# ATRACK_HOST_V1.net
KiCad netlist of a schematic drawn in Altium Designer
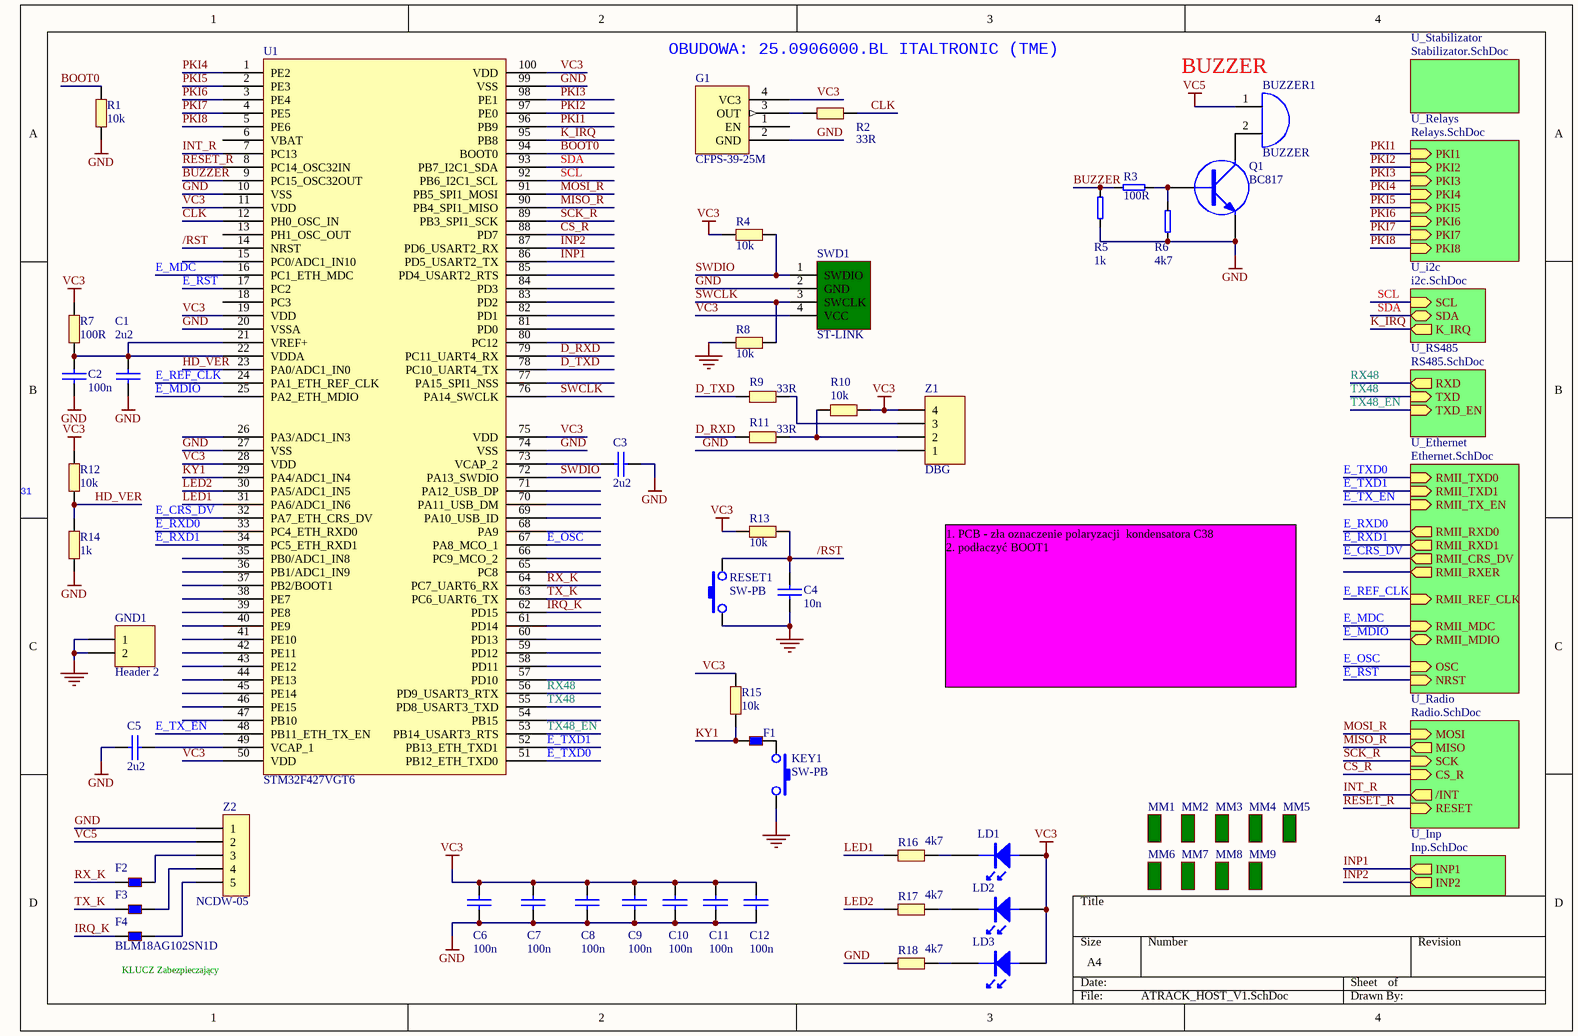
[diagram p0: ATRACK_HOST_V1.SchDoc]

(export (version "E")
  (design (tool "Eeschema 10.0.6"))
  (components
    (comp (ref "BUZZER1") (value "BUZZER") (footprint "BMT-1205H09B") (libsource (lib "*") (part "BUZZER")))
    (comp (ref "C1")
      (value "2u2")
      (footprint "0603C")
      (description "Capacitor")
      (libsource (lib "*") (part "CAP"))
    )
    (comp (ref "C2")
      (value "100n")
      (footprint "0603C")
      (description "Capacitor")
      (libsource (lib "*") (part "CAP"))
    )
    (comp (ref "C3")
      (value "2u2")
      (footprint "0603C")
      (description "Capacitor")
      (libsource (lib "*") (part "CAP"))
    )
    (comp (ref "C4")
      (value "10n")
      (footprint "0603C")
      (description "Capacitor")
      (libsource (lib "*") (part "CAP"))
    )
    (comp (ref "C5")
      (value "2u2")
      (footprint "0603C")
      (description "Capacitor")
      (libsource (lib "*") (part "CAP"))
    )
    (comp (ref "C6")
      (value "100n")
      (footprint "0603C")
      (description "Capacitor")
      (libsource (lib "*") (part "CAP"))
    )
    (comp (ref "C7")
      (value "100n")
      (footprint "0603C")
      (description "Capacitor")
      (libsource (lib "*") (part "CAP"))
    )
    (comp (ref "C8")
      (value "100n")
      (footprint "0603C")
      (description "Capacitor")
      (libsource (lib "*") (part "CAP"))
    )
    (comp (ref "C9")
      (value "100n")
      (footprint "0603C")
      (description "Capacitor")
      (libsource (lib "*") (part "CAP"))
    )
    (comp (ref "C10")
      (value "100n")
      (footprint "0603C")
      (description "Capacitor")
      (libsource (lib "*") (part "CAP"))
    )
    (comp (ref "C11")
      (value "100n")
      (footprint "0603C")
      (description "Capacitor")
      (libsource (lib "*") (part "CAP"))
    )
    (comp (ref "C12")
      (value "100n")
      (footprint "0603C")
      (description "Capacitor")
      (libsource (lib "*") (part "CAP"))
    )
    (comp (ref "F1")
      (value "BLM18BB141SN1D")
      (footprint "0603L")
      (description "Koralik ferrytowy")
      (libsource (lib "*") (part "1812"))
    )
    (comp (ref "F2")
      (value "BLM18AG102SN1D")
      (footprint "0603L")
      (description "Koralik ferrytowy")
      (libsource (lib "*") (part "KORALIK"))
    )
    (comp (ref "F3")
      (value "BLM18AG102SN1D")
      (footprint "0603L")
      (description "Koralik ferrytowy")
      (libsource (lib "*") (part "KORALIK"))
    )
    (comp (ref "F4")
      (value "BLM18AG102SN1D")
      (footprint "0603L")
      (description "Koralik ferrytowy")
      (libsource (lib "*") (part "KORALIK"))
    )
    (comp (ref "G1") (value "CFPS-39-25M") (footprint "GEN_SMD1_1") (libsource (lib "*") (part "GENER_SMD")))
    (comp (ref "GND1")
      (value "Header 2")
      (footprint "HDR1X2")
      (description "Header, 2-Pin")
      (fields (field (name "PUBLISHER") "Altium Limited"))
      (libsource (lib "Miscellaneous Connectors") (part "Header 2"))
    )
    (comp (ref "KEY1") (value "SW-PB") (footprint "DTSM31N_2") (libsource (lib "*") (part "SW-PB")))
    (comp (ref "LD1") (value "~") (footprint "0805LG") (libsource (lib "*") (part "LED")))
    (comp (ref "LD2") (value "~") (footprint "0805LR") (libsource (lib "*") (part "LED")))
    (comp (ref "LD3") (value "~") (footprint "0805LG") (libsource (lib "*") (part "LED")))
    (comp (ref "MM1") (value "~") (footprint "REF_CIR") (libsource (lib "*") (part "MECH")))
    (comp (ref "MM2") (value "~") (footprint "REF_CIR") (libsource (lib "*") (part "MECH")))
    (comp (ref "MM3") (value "~") (footprint "REF_SQR") (libsource (lib "*") (part "MECH")))
    (comp (ref "MM4") (value "~") (footprint "REF_SQR") (libsource (lib "*") (part "MECH")))
    (comp (ref "MM5") (value "~") (footprint "PB_FREE_GRAF") (libsource (lib "*") (part "MECH")))
    (comp (ref "MM6") (value "~") (footprint "REF_CIR") (libsource (lib "*") (part "MECH")))
    (comp (ref "MM7") (value "~") (footprint "REF_CIR") (libsource (lib "*") (part "MECH")))
    (comp (ref "MM8") (value "~") (footprint "REF_SQR") (libsource (lib "*") (part "MECH")))
    (comp (ref "MM9") (value "~") (footprint "REF_SQR") (libsource (lib "*") (part "MECH")))
    (comp (ref "Q1")
      (value "BC817")
      (footprint "SOT23-3Q")
      (description "NPN Transistor")
      (libsource (lib "*") (part "NPN-SOT23"))
    )
    (comp (ref "R1") (value "10k") (footprint "0603R") (libsource (lib "") (part "RES3_3")))
    (comp (ref "R2") (value "33R") (footprint "0603R") (libsource (lib "") (part "RES3_1")))
    (comp (ref "R3") (value "100R") (footprint "0603R") (libsource (lib "*") (part "R")))
    (comp (ref "R4") (value "10k") (footprint "0603R") (libsource (lib "") (part "RES3_2")))
    (comp (ref "R5") (value "1k") (footprint "0603R") (libsource (lib "*") (part "R")))
    (comp (ref "R6") (value "4k7") (footprint "0603R") (libsource (lib "*") (part "R")))
    (comp (ref "R7") (value "100R") (footprint "0603R") (libsource (lib "") (part "RES3_1")))
    (comp (ref "R8") (value "10k") (footprint "0603R") (libsource (lib "") (part "RES3_2")))
    (comp (ref "R9") (value "33R") (footprint "0603R") (libsource (lib "*") (part "RES3")))
    (comp (ref "R10") (value "10k") (footprint "0603R") (libsource (lib "") (part "RES3_2")))
    (comp (ref "R11") (value "33R") (footprint "0603R") (libsource (lib "*") (part "RES3")))
    (comp (ref "R12") (value "10k") (footprint "0603R") (libsource (lib "") (part "RES3_1")))
    (comp (ref "R13") (value "10k") (footprint "0603R") (libsource (lib "") (part "RES3_2")))
    (comp (ref "R14") (value "1k") (footprint "0603R") (libsource (lib "") (part "RES3_1")))
    (comp (ref "R15") (value "10k") (footprint "0603R") (libsource (lib "") (part "RES3_1")))
    (comp (ref "R16") (value "4k7") (footprint "0603R") (libsource (lib "*") (part "RES3")))
    (comp (ref "R17") (value "4k7") (footprint "0603R") (libsource (lib "*") (part "RES3")))
    (comp (ref "R18") (value "4k7") (footprint "0603R") (libsource (lib "*") (part "RES3")))
    (comp (ref "RESET1") (value "SW-PB") (footprint "DTSM31N_2") (libsource (lib "*") (part "SW-PB")))
    (comp (ref "SWD1")
      (value "ST-LINK")
      (footprint "PIN4")
      (description "Header, 4-Pin")
      (fields (field (name "PUBLISHER") "Altium Limited"))
      (libsource (lib "GkSchlib") (part "SW_CON"))
    )
    (comp (ref "U1")
      (value "STM32F427VGT6")
      (footprint "VQ100_2")
      (libsource (lib "GkSchlib") (part "STM32F427_LQFP100"))
    )
    (comp (ref "Z1")
      (value "DBG")
      (footprint "PIN4")
      (description "Header, 4-Pin")
      (fields (field (name "PUBLISHER") "Altium Limited"))
      (libsource (lib "Miscellaneous Connectors") (part "Header 4"))
    )
    (comp (ref "Z2")
      (value "NCDW-05")
      (footprint "KEY_LOG")
      (description "Connector")
      (libsource (lib "*") (part "CON5"))
    )
  )
  (nets
    (net (code "1") (name "/BOOT0") (class "Default")
      (node (ref "R1") (pin "1") (pintype "passive"))
      (node (ref "U1") (pin "94") (pinfunction "BOOT0_94") (pintype "passive"))
    )
    (net (code "2") (name "/BUZZER") (class "Default")
      (node (ref "R3") (pin "2") (pinfunction "2_2") (pintype "passive"))
      (node (ref "R5") (pin "1") (pinfunction "1_1") (pintype "passive"))
      (node (ref "U1") (pin "9") (pinfunction "PC15_OSC32OUT_9") (pintype "passive"))
    )
    (net (code "3") (name "/CLK") (class "Default")
      (node (ref "R2") (pin "2") (pintype "passive"))
      (node (ref "U1") (pin "12") (pinfunction "PH0_OSC_IN_12") (pintype "passive"))
    )
    (net (code "4") (name "/CS_R") (class "Default")
      (node (ref "U1") (pin "88") (pinfunction "PD7_88") (pintype "passive"))
    )
    (net (code "5") (name "/D_RXD") (class "Default")
      (node (ref "R11") (pin "2") (pintype "passive"))
      (node (ref "U1") (pin "79") (pinfunction "PC11_UART4_RX_79") (pintype "passive"))
    )
    (net (code "6") (name "/D_TXD") (class "Default")
      (node (ref "R9") (pin "2") (pintype "passive"))
      (node (ref "U1") (pin "78") (pinfunction "PC10_UART4_TX_78") (pintype "passive"))
    )
    (net (code "7") (name "/E_CRS_DV") (class "Default")
      (node (ref "U1") (pin "32") (pinfunction "PA7_ETH_CRS_DV_32") (pintype "passive"))
    )
    (net (code "8") (name "/E_MDC") (class "Default")
      (node (ref "U1") (pin "16") (pinfunction "PC1_ETH_MDC_16") (pintype "passive"))
    )
    (net (code "9") (name "/E_MDIO") (class "Default")
      (node (ref "U1") (pin "25") (pinfunction "PA2_ETH_MDIO_25") (pintype "passive"))
    )
    (net (code "10") (name "/E_OSC") (class "Default")
      (node (ref "U1") (pin "67") (pinfunction "PA8_MCO_1_67") (pintype "passive"))
    )
    (net (code "11") (name "/E_REF_CLK") (class "Default")
      (node (ref "U1") (pin "24") (pinfunction "PA1_ETH_REF_CLK_24") (pintype "passive"))
    )
    (net (code "12") (name "/E_RST") (class "Default")
      (node (ref "U1") (pin "17") (pinfunction "PC2_17") (pintype "passive"))
    )
    (net (code "13") (name "/E_RXD0") (class "Default")
      (node (ref "U1") (pin "33") (pinfunction "PC4_ETH_RXD0_33") (pintype "passive"))
    )
    (net (code "14") (name "/E_RXD1") (class "Default")
      (node (ref "U1") (pin "34") (pinfunction "PC5_ETH_RXD1_34") (pintype "passive"))
    )
    (net (code "15") (name "/E_TXD0") (class "Default")
      (node (ref "U1") (pin "51") (pinfunction "PB12_ETH_TXD0_51") (pintype "passive"))
    )
    (net (code "16") (name "/E_TXD1") (class "Default")
      (node (ref "U1") (pin "52") (pinfunction "PB13_ETH_TXD1_52") (pintype "passive"))
    )
    (net (code "17") (name "/E_TX_EN") (class "Default")
      (node (ref "U1") (pin "48") (pinfunction "PB11_ETH_TX_EN_48") (pintype "passive"))
    )
    (net (code "18") (name "/HD_VER") (class "Default")
      (node (ref "R12") (pin "1") (pintype "passive"))
      (node (ref "R14") (pin "2") (pintype "passive"))
      (node (ref "U1") (pin "23") (pinfunction "PA0/ADC1_IN0_23") (pintype "passive"))
    )
    (net (code "19") (name "/INP1") (class "Default")
      (node (ref "U1") (pin "86") (pinfunction "PD5_USART2_TX_86") (pintype "passive"))
    )
    (net (code "20") (name "/INP2") (class "Default")
      (node (ref "U1") (pin "87") (pinfunction "PD6_USART2_RX_87") (pintype "passive"))
    )
    (net (code "21") (name "/INT_R") (class "Default")
      (node (ref "U1") (pin "7") (pinfunction "PC13_7") (pintype "passive"))
    )
    (net (code "22") (name "/IRQ_K") (class "Default")
      (node (ref "F4") (pin "1") (pintype "passive"))
      (node (ref "U1") (pin "62") (pinfunction "PD15_62") (pintype "passive"))
    )
    (net (code "23") (name "/KY1") (class "Default")
      (node (ref "F1") (pin "2") (pintype "passive"))
      (node (ref "R15") (pin "1") (pintype "passive"))
      (node (ref "U1") (pin "29") (pinfunction "PA4/ADC1_IN4_29") (pintype "passive"))
    )
    (net (code "24") (name "/K_IRQ") (class "Default")
      (node (ref "U1") (pin "95") (pinfunction "PB8_95") (pintype "passive"))
    )
    (net (code "25") (name "/LED1") (class "Default")
      (node (ref "R16") (pin "2") (pintype "passive"))
      (node (ref "U1") (pin "31") (pinfunction "PA6/ADC1_IN6_31") (pintype "passive"))
    )
    (net (code "26") (name "/LED2") (class "Default")
      (node (ref "R17") (pin "2") (pintype "passive"))
      (node (ref "U1") (pin "30") (pinfunction "PA5/ADC1_IN5_30") (pintype "passive"))
    )
    (net (code "27") (name "/MISO_R") (class "Default")
      (node (ref "U1") (pin "90") (pinfunction "PB4_SPI1_MISO_90") (pintype "passive"))
    )
    (net (code "28") (name "/MOSI_R") (class "Default")
      (node (ref "U1") (pin "91") (pinfunction "PB5_SPI1_MOSI_91") (pintype "passive"))
    )
    (net (code "29") (name "/PKI1") (class "Default")
      (node (ref "U1") (pin "96") (pinfunction "PB9_96") (pintype "passive"))
    )
    (net (code "30") (name "/PKI2") (class "Default")
      (node (ref "U1") (pin "97") (pinfunction "PE0_97") (pintype "passive"))
    )
    (net (code "31") (name "/PKI3") (class "Default")
      (node (ref "U1") (pin "98") (pinfunction "PE1_98") (pintype "passive"))
    )
    (net (code "32") (name "/PKI4") (class "Default")
      (node (ref "U1") (pin "1") (pinfunction "PE2_1") (pintype "passive"))
    )
    (net (code "33") (name "/PKI5") (class "Default")
      (node (ref "U1") (pin "2") (pinfunction "PE3_2") (pintype "passive"))
    )
    (net (code "34") (name "/PKI6") (class "Default")
      (node (ref "U1") (pin "3") (pinfunction "PE4_3") (pintype "passive"))
    )
    (net (code "35") (name "/PKI7") (class "Default")
      (node (ref "U1") (pin "4") (pinfunction "PE5_4") (pintype "passive"))
    )
    (net (code "36") (name "/PKI8") (class "Default")
      (node (ref "U1") (pin "5") (pinfunction "PE6_5") (pintype "passive"))
    )
    (net (code "37") (name "/RESET_R") (class "Default")
      (node (ref "U1") (pin "8") (pinfunction "PC14_OSC32IN_8") (pintype "passive"))
    )
    (net (code "39") (name "/RX48") (class "Default")
      (node (ref "U1") (pin "56") (pinfunction "PD9_USART3_RTX_56") (pintype "passive"))
    )
    (net (code "40") (name "/RX_K") (class "Default")
      (node (ref "F2") (pin "1") (pintype "passive"))
      (node (ref "U1") (pin "64") (pinfunction "PC7_UART6_RX_64") (pintype "passive"))
    )
    (net (code "41") (name "/SCK_R") (class "Default")
      (node (ref "U1") (pin "89") (pinfunction "PB3_SPI1_SCK_89") (pintype "passive"))
    )
    (net (code "42") (name "/SCL") (class "Default")
      (node (ref "U1") (pin "92") (pinfunction "PB6_I2C1_SCL_92") (pintype "passive"))
    )
    (net (code "43") (name "/SDA") (class "Default")
      (node (ref "U1") (pin "93") (pinfunction "PB7_I2C1_SDA_93") (pintype "passive"))
    )
    (net (code "44") (name "/SWCLK") (class "Default")
      (node (ref "R8") (pin "2") (pintype "passive"))
      (node (ref "SWD1") (pin "3") (pinfunction "SWCLK_3") (pintype "passive"))
      (node (ref "U1") (pin "76") (pinfunction "PA14_SWCLK_76") (pintype "passive"))
    )
    (net (code "45") (name "/SWDIO") (class "Default")
      (node (ref "R4") (pin "2") (pintype "passive"))
      (node (ref "SWD1") (pin "1") (pinfunction "SWDIO_1") (pintype "passive"))
      (node (ref "U1") (pin "72") (pinfunction "PA13_SWDIO_72") (pintype "passive"))
    )
    (net (code "46") (name "/TX48") (class "Default")
      (node (ref "U1") (pin "55") (pinfunction "PD8_USART3_TXD_55") (pintype "passive"))
    )
    (net (code "47") (name "/TX48_EN") (class "Default")
      (node (ref "U1") (pin "53") (pinfunction "PB14_USART3_RTS_53") (pintype "passive"))
    )
    (net (code "48") (name "/TX_K") (class "Default")
      (node (ref "F3") (pin "1") (pintype "passive"))
      (node (ref "U1") (pin "63") (pinfunction "PC6_UART6_TX_63") (pintype "passive"))
    )
    (net (code "49") (name "/{slash}RST") (class "Default")
      (node (ref "C4") (pin "1") (pinfunction "1_1") (pintype "passive"))
      (node (ref "R13") (pin "2") (pintype "passive"))
      (node (ref "RESET1") (pin "2") (pinfunction "2_2") (pintype "passive"))
      (node (ref "U1") (pin "14") (pinfunction "NRST_14") (pintype "passive"))
    )
    (net (code "50") (name "GND") (class "Default")
      (node (ref "C1") (pin "2") (pinfunction "2_2") (pintype "passive"))
      (node (ref "C10") (pin "2") (pinfunction "2_2") (pintype "passive"))
      (node (ref "C11") (pin "2") (pinfunction "2_2") (pintype "passive"))
      (node (ref "C12") (pin "2") (pinfunction "2_2") (pintype "passive"))
      (node (ref "C2") (pin "2") (pinfunction "2_2") (pintype "passive"))
      (node (ref "C3") (pin "1") (pinfunction "1_1") (pintype "passive"))
      (node (ref "C4") (pin "2") (pinfunction "2_2") (pintype "passive"))
      (node (ref "C5") (pin "1") (pinfunction "1_1") (pintype "passive"))
      (node (ref "C6") (pin "2") (pinfunction "2_2") (pintype "passive"))
      (node (ref "C7") (pin "2") (pinfunction "2_2") (pintype "passive"))
      (node (ref "C8") (pin "2") (pinfunction "2_2") (pintype "passive"))
      (node (ref "C9") (pin "2") (pinfunction "2_2") (pintype "passive"))
      (node (ref "G1") (pin "2") (pinfunction "GND_2") (pintype "power_in"))
      (node (ref "GND1") (pin "1") (pinfunction "1_1") (pintype "passive"))
      (node (ref "GND1") (pin "2") (pinfunction "2_2") (pintype "passive"))
      (node (ref "KEY1") (pin "2") (pinfunction "2_2") (pintype "passive"))
      (node (ref "Q1") (pin "E") (pinfunction "E_E") (pintype "passive"))
      (node (ref "R1") (pin "2") (pintype "passive"))
      (node (ref "R14") (pin "1") (pintype "passive"))
      (node (ref "R18") (pin "2") (pintype "passive"))
      (node (ref "R5") (pin "2") (pinfunction "2_2") (pintype "passive"))
      (node (ref "R6") (pin "2") (pinfunction "2_2") (pintype "passive"))
      (node (ref "R8") (pin "1") (pintype "passive"))
      (node (ref "RESET1") (pin "1") (pinfunction "1_1") (pintype "passive"))
      (node (ref "SWD1") (pin "2") (pinfunction "GND_2") (pintype "passive"))
      (node (ref "U1") (pin "10") (pinfunction "VSS_10") (pintype "passive"))
      (node (ref "U1") (pin "20") (pinfunction "VSSA_20") (pintype "passive"))
      (node (ref "U1") (pin "27") (pinfunction "VSS_27") (pintype "passive"))
      (node (ref "U1") (pin "74") (pinfunction "VSS_74") (pintype "passive"))
      (node (ref "U1") (pin "99") (pinfunction "VSS_99") (pintype "passive"))
      (node (ref "Z1") (pin "1") (pinfunction "1_1") (pintype "passive"))
      (node (ref "Z2") (pin "1") (pinfunction "1_1") (pintype "passive"))
    )
    (net (code "51") (name "Net-(BUZZER1-Pad2)") (class "Default")
      (node (ref "BUZZER1") (pin "2") (pinfunction "2_2") (pintype "passive"))
      (node (ref "Q1") (pin "C") (pinfunction "C_C") (pintype "passive"))
    )
    (net (code "52") (name "Net-(F1-Pad1)") (class "Default")
      (node (ref "F1") (pin "1") (pintype "passive"))
      (node (ref "KEY1") (pin "1") (pinfunction "1_1") (pintype "passive"))
    )
    (net (code "53") (name "Net-(F2-Pad2)") (class "Default")
      (node (ref "F2") (pin "2") (pintype "passive"))
      (node (ref "Z2") (pin "3") (pinfunction "3_3") (pintype "passive"))
    )
    (net (code "54") (name "Net-(F3-Pad2)") (class "Default")
      (node (ref "F3") (pin "2") (pintype "passive"))
      (node (ref "Z2") (pin "4") (pinfunction "4_4") (pintype "passive"))
    )
    (net (code "55") (name "Net-(F4-Pad2)") (class "Default")
      (node (ref "F4") (pin "2") (pintype "passive"))
      (node (ref "Z2") (pin "5") (pinfunction "5_5") (pintype "passive"))
    )
    (net (code "56") (name "Net-(G1-OUT)") (class "Default")
      (node (ref "G1") (pin "3") (pinfunction "OUT_3") (pintype "output"))
      (node (ref "R2") (pin "1") (pintype "passive"))
    )
    (net (code "57") (name "Net-(LD1-2)") (class "Default")
      (node (ref "LD1") (pin "K") (pinfunction "2_K") (pintype "passive"))
      (node (ref "R16") (pin "1") (pintype "passive"))
    )
    (net (code "58") (name "Net-(LD2-2)") (class "Default")
      (node (ref "LD2") (pin "K") (pinfunction "2_K") (pintype "passive"))
      (node (ref "R17") (pin "1") (pintype "passive"))
    )
    (net (code "59") (name "Net-(LD3-2)") (class "Default")
      (node (ref "LD3") (pin "K") (pinfunction "2_K") (pintype "passive"))
      (node (ref "R18") (pin "1") (pintype "passive"))
    )
    (net (code "60") (name "Net-(Q1-PadB)") (class "Default")
      (node (ref "Q1") (pin "B") (pinfunction "B_B") (pintype "passive"))
      (node (ref "R3") (pin "1") (pinfunction "1_1") (pintype "passive"))
      (node (ref "R6") (pin "1") (pinfunction "1_1") (pintype "passive"))
    )
    (net (code "61") (name "Net-(R9-Pad1)") (class "Default")
      (node (ref "R9") (pin "1") (pintype "passive"))
      (node (ref "Z1") (pin "3") (pinfunction "3_3") (pintype "passive"))
    )
    (net (code "62") (name "Net-(R10-Pad1)") (class "Default")
      (node (ref "R10") (pin "1") (pintype "passive"))
      (node (ref "R11") (pin "1") (pintype "passive"))
      (node (ref "Z1") (pin "2") (pinfunction "2_2") (pintype "passive"))
    )
    (net (code "63") (name "Net-(U1-VCAP_1)") (class "Default")
      (node (ref "C5") (pin "2") (pinfunction "2_2") (pintype "passive"))
      (node (ref "U1") (pin "49") (pinfunction "VCAP_1_49") (pintype "passive"))
    )
    (net (code "64") (name "Net-(U1-VCAP_2)") (class "Default")
      (node (ref "C3") (pin "2") (pinfunction "2_2") (pintype "passive"))
      (node (ref "U1") (pin "73") (pinfunction "VCAP_2_73") (pintype "passive"))
    )
    (net (code "65") (name "Net-(U1-VDDA)") (class "Default")
      (node (ref "C1") (pin "1") (pinfunction "1_1") (pintype "passive"))
      (node (ref "C2") (pin "1") (pinfunction "1_1") (pintype "passive"))
      (node (ref "R7") (pin "1") (pintype "passive"))
      (node (ref "U1") (pin "21") (pinfunction "VREF+_21") (pintype "passive"))
      (node (ref "U1") (pin "22") (pinfunction "VDDA_22") (pintype "passive"))
    )
    (net (code "66") (name "VC3") (class "Default")
      (node (ref "C10") (pin "1") (pinfunction "1_1") (pintype "passive"))
      (node (ref "C11") (pin "1") (pinfunction "1_1") (pintype "passive"))
      (node (ref "C12") (pin "1") (pinfunction "1_1") (pintype "passive"))
      (node (ref "C6") (pin "1") (pinfunction "1_1") (pintype "passive"))
      (node (ref "C7") (pin "1") (pinfunction "1_1") (pintype "passive"))
      (node (ref "C8") (pin "1") (pinfunction "1_1") (pintype "passive"))
      (node (ref "C9") (pin "1") (pinfunction "1_1") (pintype "passive"))
      (node (ref "G1") (pin "4") (pinfunction "VC3_4") (pintype "power_in"))
      (node (ref "LD1") (pin "A") (pinfunction "1_A") (pintype "passive"))
      (node (ref "LD2") (pin "A") (pinfunction "1_A") (pintype "passive"))
      (node (ref "LD3") (pin "A") (pinfunction "1_A") (pintype "passive"))
      (node (ref "R10") (pin "2") (pintype "passive"))
      (node (ref "R12") (pin "2") (pintype "passive"))
      (node (ref "R13") (pin "1") (pintype "passive"))
      (node (ref "R15") (pin "2") (pintype "passive"))
      (node (ref "R4") (pin "1") (pintype "passive"))
      (node (ref "R7") (pin "2") (pintype "passive"))
      (node (ref "SWD1") (pin "4") (pinfunction "VCC_4") (pintype "passive"))
      (node (ref "U1") (pin "100") (pinfunction "VDD_100") (pintype "passive"))
      (node (ref "U1") (pin "11") (pinfunction "VDD_11") (pintype "passive"))
      (node (ref "U1") (pin "19") (pinfunction "VDD_19") (pintype "passive"))
      (node (ref "U1") (pin "28") (pinfunction "VDD_28") (pintype "passive"))
      (node (ref "U1") (pin "50") (pinfunction "VDD_50") (pintype "passive"))
      (node (ref "U1") (pin "75") (pinfunction "VDD_75") (pintype "passive"))
      (node (ref "Z1") (pin "4") (pinfunction "4_4") (pintype "passive"))
    )
    (net (code "67") (name "VC5") (class "Default")
      (node (ref "BUZZER1") (pin "1") (pinfunction "1_1") (pintype "passive"))
      (node (ref "Z2") (pin "2") (pinfunction "2_2") (pintype "passive"))
    )
    (net (code "68") (name "unconnected-(G1-EN-Pad1)") (class "Default")
      (node (ref "G1") (pin "1") (pinfunction "EN_1") (pintype "passive"))
    )
    (net (code "69") (name "unconnected-(U1-PA3{slash}ADC1_IN3-Pad26)") (class "Default")
      (node (ref "U1") (pin "26") (pinfunction "PA3/ADC1_IN3_26") (pintype "passive"))
    )
    (net (code "70") (name "unconnected-(U1-PA9-Pad68)") (class "Default")
      (node (ref "U1") (pin "68") (pinfunction "PA9_68") (pintype "passive"))
    )
    (net (code "71") (name "unconnected-(U1-PA10_USB_ID-Pad69)") (class "Default")
      (node (ref "U1") (pin "69") (pinfunction "PA10_USB_ID_69") (pintype "passive"))
    )
    (net (code "72") (name "unconnected-(U1-PA11_USB_DM-Pad70)") (class "Default")
      (node (ref "U1") (pin "70") (pinfunction "PA11_USB_DM_70") (pintype "passive"))
    )
    (net (code "73") (name "unconnected-(U1-PA12_USB_DP-Pad71)") (class "Default")
      (node (ref "U1") (pin "71") (pinfunction "PA12_USB_DP_71") (pintype "passive"))
    )
    (net (code "74") (name "unconnected-(U1-PA15_SPI1_NSS-Pad77)") (class "Default")
      (node (ref "U1") (pin "77") (pinfunction "PA15_SPI1_NSS_77") (pintype "passive"))
    )
    (net (code "75") (name "unconnected-(U1-PB0{slash}ADC1_IN8-Pad35)") (class "Default")
      (node (ref "U1") (pin "35") (pinfunction "PB0/ADC1_IN8_35") (pintype "passive"))
    )
    (net (code "76") (name "unconnected-(U1-PB1{slash}ADC1_IN9-Pad36)") (class "Default")
      (node (ref "U1") (pin "36") (pinfunction "PB1/ADC1_IN9_36") (pintype "passive"))
    )
    (net (code "77") (name "unconnected-(U1-PB2{slash}BOOT1-Pad37)") (class "Default")
      (node (ref "U1") (pin "37") (pinfunction "PB2/BOOT1_37") (pintype "passive"))
    )
    (net (code "78") (name "unconnected-(U1-PB10-Pad47)") (class "Default")
      (node (ref "U1") (pin "47") (pinfunction "PB10_47") (pintype "passive"))
    )
    (net (code "79") (name "unconnected-(U1-PB15-Pad54)") (class "Default")
      (node (ref "U1") (pin "54") (pinfunction "PB15_54") (pintype "passive"))
    )
    (net (code "80") (name "unconnected-(U1-PC0{slash}ADC1_IN10-Pad15)") (class "Default")
      (node (ref "U1") (pin "15") (pinfunction "PC0/ADC1_IN10_15") (pintype "passive"))
    )
    (net (code "81") (name "unconnected-(U1-PC3-Pad18)") (class "Default")
      (node (ref "U1") (pin "18") (pinfunction "PC3_18") (pintype "passive"))
    )
    (net (code "82") (name "unconnected-(U1-PC8-Pad65)") (class "Default")
      (node (ref "U1") (pin "65") (pinfunction "PC8_65") (pintype "passive"))
    )
    (net (code "83") (name "unconnected-(U1-PC9_MCO_2-Pad66)") (class "Default")
      (node (ref "U1") (pin "66") (pinfunction "PC9_MCO_2_66") (pintype "passive"))
    )
    (net (code "84") (name "unconnected-(U1-PC12-Pad80)") (class "Default")
      (node (ref "U1") (pin "80") (pinfunction "PC12_80") (pintype "passive"))
    )
    (net (code "85") (name "unconnected-(U1-PD0-Pad81)") (class "Default")
      (node (ref "U1") (pin "81") (pinfunction "PD0_81") (pintype "passive"))
    )
    (net (code "86") (name "unconnected-(U1-PD1-Pad82)") (class "Default")
      (node (ref "U1") (pin "82") (pinfunction "PD1_82") (pintype "passive"))
    )
    (net (code "87") (name "unconnected-(U1-PD2-Pad83)") (class "Default")
      (node (ref "U1") (pin "83") (pinfunction "PD2_83") (pintype "passive"))
    )
    (net (code "88") (name "unconnected-(U1-PD3-Pad84)") (class "Default")
      (node (ref "U1") (pin "84") (pinfunction "PD3_84") (pintype "passive"))
    )
    (net (code "89") (name "unconnected-(U1-PD4_USART2_RTS-Pad85)") (class "Default")
      (node (ref "U1") (pin "85") (pinfunction "PD4_USART2_RTS_85") (pintype "passive"))
    )
    (net (code "90") (name "unconnected-(U1-PD10-Pad57)") (class "Default")
      (node (ref "U1") (pin "57") (pinfunction "PD10_57") (pintype "passive"))
    )
    (net (code "91") (name "unconnected-(U1-PD11-Pad58)") (class "Default")
      (node (ref "U1") (pin "58") (pinfunction "PD11_58") (pintype "passive"))
    )
    (net (code "92") (name "unconnected-(U1-PD12-Pad59)") (class "Default")
      (node (ref "U1") (pin "59") (pinfunction "PD12_59") (pintype "passive"))
    )
    (net (code "93") (name "unconnected-(U1-PD13-Pad60)") (class "Default")
      (node (ref "U1") (pin "60") (pinfunction "PD13_60") (pintype "passive"))
    )
    (net (code "94") (name "unconnected-(U1-PD14-Pad61)") (class "Default")
      (node (ref "U1") (pin "61") (pinfunction "PD14_61") (pintype "passive"))
    )
    (net (code "95") (name "unconnected-(U1-PE7-Pad38)") (class "Default")
      (node (ref "U1") (pin "38") (pinfunction "PE7_38") (pintype "passive"))
    )
    (net (code "96") (name "unconnected-(U1-PE8-Pad39)") (class "Default")
      (node (ref "U1") (pin "39") (pinfunction "PE8_39") (pintype "passive"))
    )
    (net (code "97") (name "unconnected-(U1-PE9-Pad40)") (class "Default")
      (node (ref "U1") (pin "40") (pinfunction "PE9_40") (pintype "passive"))
    )
    (net (code "98") (name "unconnected-(U1-PE10-Pad41)") (class "Default")
      (node (ref "U1") (pin "41") (pinfunction "PE10_41") (pintype "passive"))
    )
    (net (code "99") (name "unconnected-(U1-PE11-Pad42)") (class "Default")
      (node (ref "U1") (pin "42") (pinfunction "PE11_42") (pintype "passive"))
    )
    (net (code "100") (name "unconnected-(U1-PE12-Pad43)") (class "Default")
      (node (ref "U1") (pin "43") (pinfunction "PE12_43") (pintype "passive"))
    )
    (net (code "101") (name "unconnected-(U1-PE13-Pad44)") (class "Default")
      (node (ref "U1") (pin "44") (pinfunction "PE13_44") (pintype "passive"))
    )
    (net (code "102") (name "unconnected-(U1-PE14-Pad45)") (class "Default")
      (node (ref "U1") (pin "45") (pinfunction "PE14_45") (pintype "passive"))
    )
    (net (code "103") (name "unconnected-(U1-PE15-Pad46)") (class "Default")
      (node (ref "U1") (pin "46") (pinfunction "PE15_46") (pintype "passive"))
    )
    (net (code "104") (name "unconnected-(U1-PH1_OSC_OUT-Pad13)") (class "Default")
      (node (ref "U1") (pin "13") (pinfunction "PH1_OSC_OUT_13") (pintype "passive"))
    )
    (net (code "105") (name "unconnected-(U1-VBAT-Pad6)") (class "Default")
      (node (ref "U1") (pin "6") (pinfunction "VBAT_6") (pintype "passive"))
    )
  )
)
